# xbee_breakout.net
KiCad netlist of a schematic drawn in EAGLE
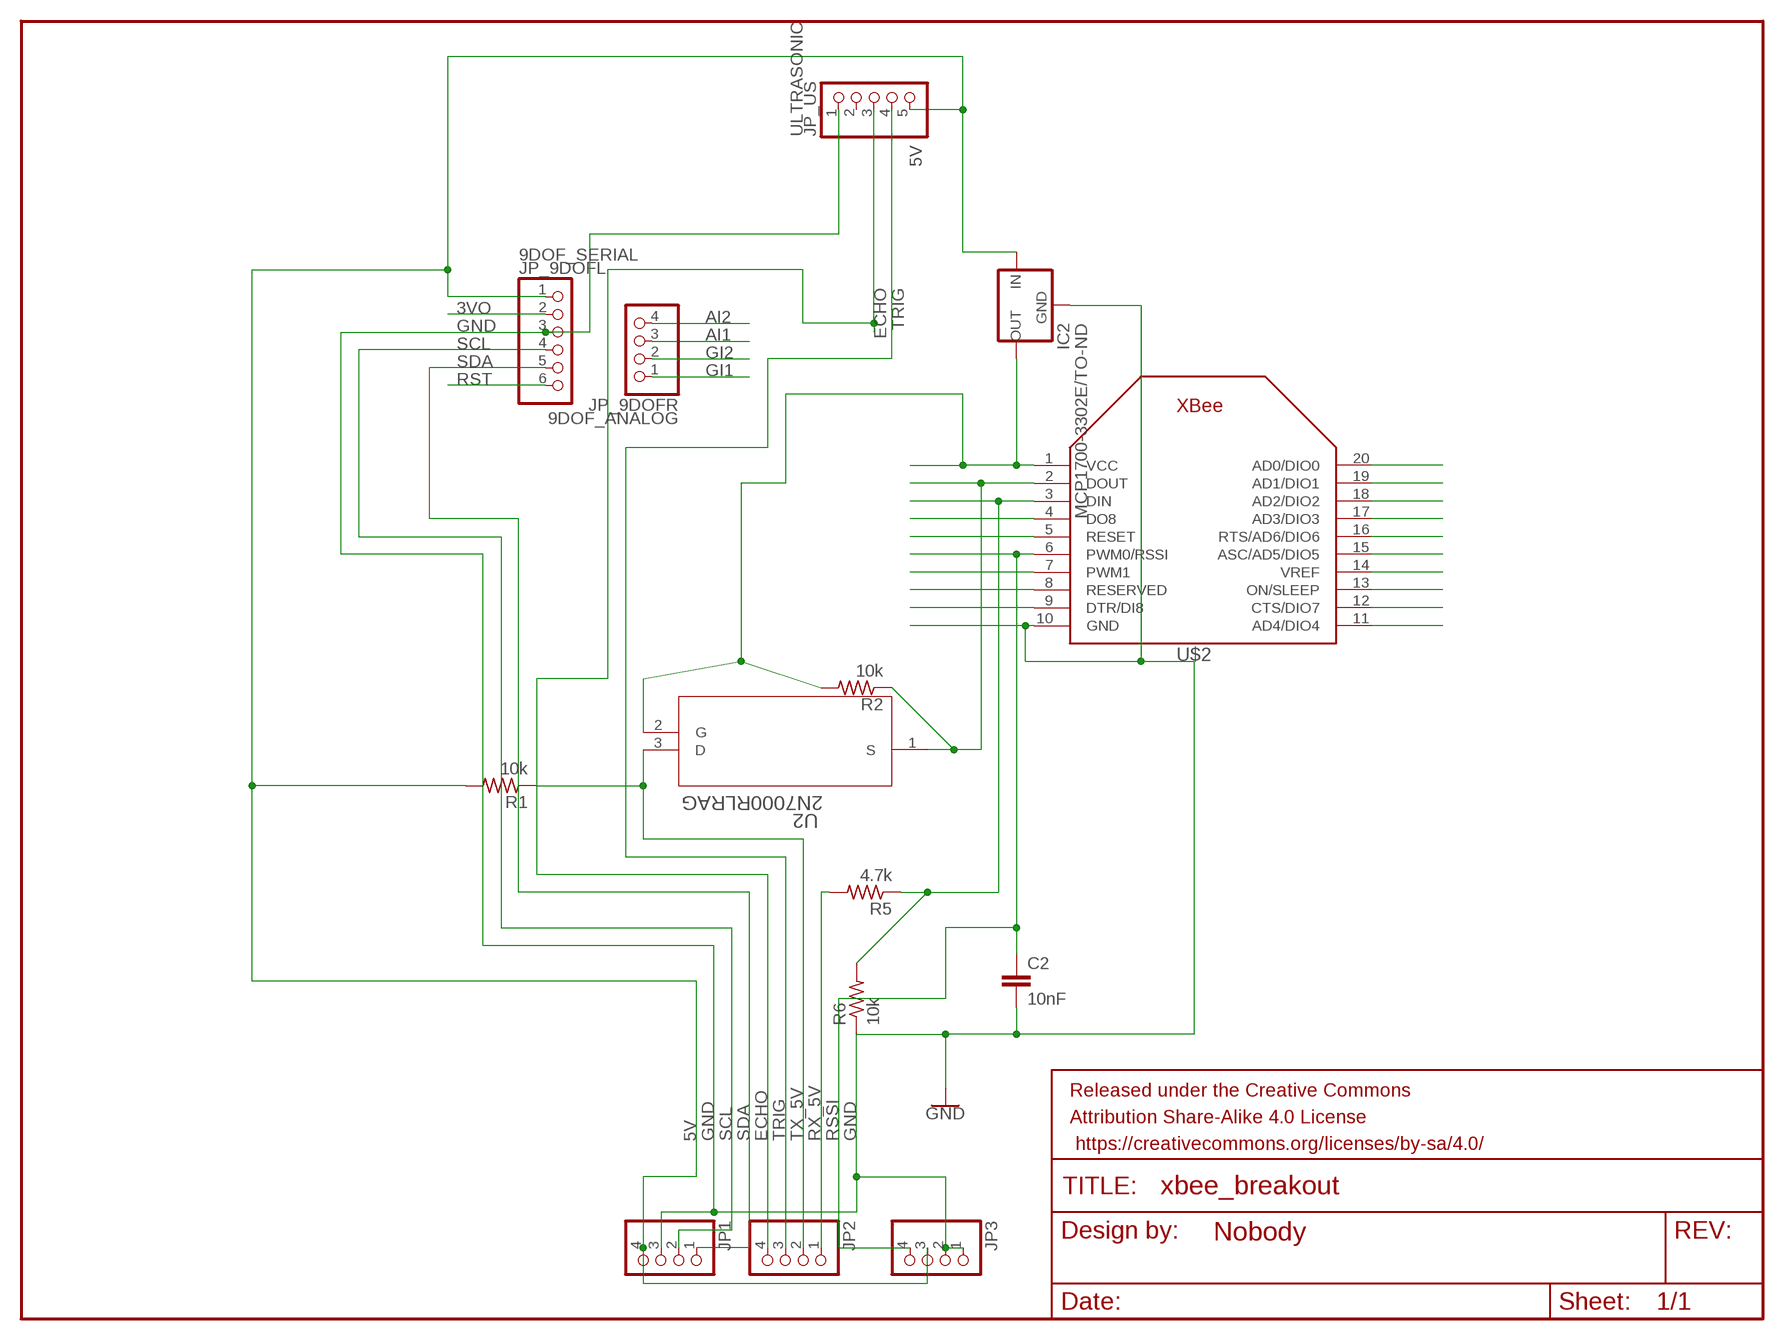
[diagram p0: schematic, sheet 1]

(export (version "E")
  (design (tool "Eeschema 10.0.6"))
  (components
    (comp (ref "C2")
      (value "10nF")
      (footprint "eagle-import:CAP-PTH-10MM")
      (libsource (lib "eagle-import") (part "10NF-PTH-10MM-10000V-1-%"))
    )
    (comp (ref "FRAME1")
      (value "FRAME-LETTERNO_PACKAGE")
      (footprint "eagle-import:DUMMY")
      (fields (field (name "DESIGNER") "Nobody"))
      (libsource (lib "eagle-import") (part "FRAME-LETTERNO_PACKAGE"))
    )
    (comp (ref "IC2")
      (value "MCP1700-3302E/TO-ND")
      (footprint "eagle-import:TO92-INLINE")
      (libsource (lib "eagle-import") (part "MCP1700INLINE"))
    )
    (comp (ref "JP1")
      (value "PINHD-1X4")
      (footprint "eagle-import:1X04")
      (libsource (lib "eagle-import") (part "PINHD-1X4"))
    )
    (comp (ref "JP2")
      (value "PINHD-1X4")
      (footprint "eagle-import:1X04")
      (libsource (lib "eagle-import") (part "PINHD-1X4"))
    )
    (comp (ref "JP3")
      (value "PINHD-1X4")
      (footprint "eagle-import:1X04")
      (libsource (lib "eagle-import") (part "PINHD-1X4"))
    )
    (comp (ref "JP_9DOFL")
      (value "PINHD-1X6")
      (footprint "eagle-import:1X06")
      (libsource (lib "eagle-import") (part "PINHD-1X6"))
    )
    (comp (ref "JP_9DOFR")
      (value "PINHD-1X4")
      (footprint "eagle-import:1X04")
      (libsource (lib "eagle-import") (part "PINHD-1X4"))
    )
    (comp (ref "JP_US")
      (value "PINHD-1X5")
      (footprint "eagle-import:1X05")
      (libsource (lib "eagle-import") (part "PINHD-1X5"))
    )
    (comp (ref "R1")
      (value "10k")
      (footprint "eagle-import:0207_12")
      (libsource (lib "eagle-import") (part "R-US_0207/12"))
    )
    (comp (ref "R2")
      (value "10k")
      (footprint "eagle-import:0207_12")
      (libsource (lib "eagle-import") (part "R-US_0207/12"))
    )
    (comp (ref "R5")
      (value "4.7k")
      (footprint "eagle-import:0207_12")
      (libsource (lib "eagle-import") (part "R-US_0207/12"))
    )
    (comp (ref "R6")
      (value "10k")
      (footprint "eagle-import:0207_12")
      (libsource (lib "eagle-import") (part "R-US_0207/12"))
    )
    (comp (ref "U$2")
      (value "XBEE")
      (footprint "eagle-import:XBEE")
      (libsource (lib "eagle-import") (part "XBEE"))
    )
    (comp (ref "U2")
      (value "2N7000RLRAG")
      (footprint "eagle-import:TO-92")
      (libsource (lib "eagle-import") (part "2N7000RLRAG"))
    )
  )
  (nets
    (net (code "1") (name "/3VO") (class "Default")
      (node (ref "JP_9DOFL") (pin "2") (pinfunction "2_2") (pintype "passive"))
    )
    (net (code "2") (name "/5V") (class "Default")
      (node (ref "IC2") (pin "2") (pinfunction "IN_2") (pintype "input"))
      (node (ref "JP1") (pin "4") (pinfunction "4_4") (pintype "passive"))
      (node (ref "JP3") (pin "3") (pinfunction "3_3") (pintype "passive"))
      (node (ref "JP_9DOFL") (pin "1") (pinfunction "1_1") (pintype "passive"))
      (node (ref "JP_US") (pin "5") (pinfunction "5_5") (pintype "passive"))
      (node (ref "R1") (pin "2") (pinfunction "2_2") (pintype "passive"))
    )
    (net (code "3") (name "/AI1") (class "Default")
      (node (ref "JP_9DOFR") (pin "3") (pinfunction "3_3") (pintype "passive"))
    )
    (net (code "4") (name "/AI2") (class "Default")
      (node (ref "JP_9DOFR") (pin "4") (pinfunction "4_4") (pintype "passive"))
    )
    (net (code "5") (name "/ECHO") (class "Default")
      (node (ref "JP2") (pin "4") (pinfunction "4_4") (pintype "passive"))
      (node (ref "JP_US") (pin "3") (pinfunction "3_3") (pintype "passive"))
    )
    (net (code "6") (name "/GI1") (class "Default")
      (node (ref "JP_9DOFR") (pin "1") (pinfunction "1_1") (pintype "passive"))
    )
    (net (code "7") (name "/GI2") (class "Default")
      (node (ref "JP_9DOFR") (pin "2") (pinfunction "2_2") (pintype "passive"))
    )
    (net (code "8") (name "/RSSI") (class "Default")
      (node (ref "C2") (pin "1") (pinfunction "1_1") (pintype "passive"))
      (node (ref "JP3") (pin "4") (pinfunction "4_4") (pintype "passive"))
      (node (ref "U$2") (pin "6") (pinfunction "PWM0/RSSI_6") (pintype "output"))
    )
    (net (code "9") (name "/RST") (class "Default")
      (node (ref "JP_9DOFL") (pin "6") (pinfunction "6_6") (pintype "passive"))
    )
    (net (code "10") (name "/RX_5V") (class "Default")
      (node (ref "JP2") (pin "1") (pinfunction "1_1") (pintype "passive"))
      (node (ref "R5") (pin "2") (pinfunction "2_2") (pintype "passive"))
    )
    (net (code "11") (name "/SCL") (class "Default")
      (node (ref "JP1") (pin "2") (pinfunction "2_2") (pintype "passive"))
      (node (ref "JP_9DOFL") (pin "4") (pinfunction "4_4") (pintype "passive"))
    )
    (net (code "12") (name "/SDA") (class "Default")
      (node (ref "JP1") (pin "1") (pinfunction "1_1") (pintype "passive"))
      (node (ref "JP_9DOFL") (pin "5") (pinfunction "5_5") (pintype "passive"))
    )
    (net (code "13") (name "/TRIG") (class "Default")
      (node (ref "JP2") (pin "3") (pinfunction "3_3") (pintype "passive"))
      (node (ref "JP_US") (pin "4") (pinfunction "4_4") (pintype "passive"))
    )
    (net (code "14") (name "/TX_5V") (class "Default")
      (node (ref "JP2") (pin "2") (pinfunction "2_2") (pintype "passive"))
      (node (ref "R1") (pin "1") (pinfunction "1_1") (pintype "passive"))
      (node (ref "U2") (pin "3") (pinfunction "D_3") (pintype "passive"))
    )
    (net (code "15") (name "GND") (class "Default")
      (node (ref "C2") (pin "2") (pinfunction "2_2") (pintype "passive"))
      (node (ref "IC2") (pin "1") (pinfunction "GND_1") (pintype "input"))
      (node (ref "JP1") (pin "3") (pinfunction "3_3") (pintype "passive"))
      (node (ref "JP3") (pin "1") (pinfunction "1_1") (pintype "passive"))
      (node (ref "JP3") (pin "2") (pinfunction "2_2") (pintype "passive"))
      (node (ref "JP_9DOFL") (pin "3") (pinfunction "3_3") (pintype "passive"))
      (node (ref "JP_US") (pin "1") (pinfunction "1_1") (pintype "passive"))
      (node (ref "R6") (pin "1") (pinfunction "1_1") (pintype "passive"))
      (node (ref "U$2") (pin "10") (pinfunction "GND_10") (pintype "power_in"))
    )
    (net (code "16") (name "Net-(IC2-OUT)") (class "Default")
      (node (ref "IC2") (pin "3") (pinfunction "OUT_3") (pintype "passive"))
      (node (ref "R2") (pin "2") (pinfunction "2_2") (pintype "passive"))
      (node (ref "U$2") (pin "1") (pinfunction "VCC_1") (pintype "power_in"))
      (node (ref "U2") (pin "2") (pinfunction "G_2") (pintype "passive"))
    )
    (net (code "17") (name "Net-(U$2-DIN)") (class "Default")
      (node (ref "R5") (pin "1") (pinfunction "1_1") (pintype "passive"))
      (node (ref "R6") (pin "2") (pinfunction "2_2") (pintype "passive"))
      (node (ref "U$2") (pin "3") (pinfunction "DIN_3") (pintype "input"))
    )
    (net (code "18") (name "Net-(U$2-DOUT)") (class "Default")
      (node (ref "R2") (pin "1") (pinfunction "1_1") (pintype "passive"))
      (node (ref "U$2") (pin "2") (pinfunction "DOUT_2") (pintype "output"))
      (node (ref "U2") (pin "1") (pinfunction "S_1") (pintype "passive"))
    )
    (net (code "19") (name "unconnected-(JP_US-Pad2)") (class "Default")
      (node (ref "JP_US") (pin "2") (pinfunction "2_2") (pintype "passive"))
    )
    (net (code "20") (name "unconnected-(U$2-AD0{slash}DIO0-Pad20)") (class "Default")
      (node (ref "U$2") (pin "20") (pinfunction "AD0/DIO0_20") (pintype "bidirectional"))
    )
    (net (code "21") (name "unconnected-(U$2-AD1{slash}DIO1-Pad19)") (class "Default")
      (node (ref "U$2") (pin "19") (pinfunction "AD1/DIO1_19") (pintype "bidirectional"))
    )
    (net (code "22") (name "unconnected-(U$2-AD2{slash}DIO2-Pad18)") (class "Default")
      (node (ref "U$2") (pin "18") (pinfunction "AD2/DIO2_18") (pintype "bidirectional"))
    )
    (net (code "23") (name "unconnected-(U$2-AD3{slash}DIO3-Pad17)") (class "Default")
      (node (ref "U$2") (pin "17") (pinfunction "AD3/DIO3_17") (pintype "bidirectional"))
    )
    (net (code "24") (name "unconnected-(U$2-AD4{slash}DIO4-Pad11)") (class "Default")
      (node (ref "U$2") (pin "11") (pinfunction "AD4/DIO4_11") (pintype "bidirectional"))
    )
    (net (code "25") (name "unconnected-(U$2-ASC{slash}AD5{slash}DIO5-Pad15)") (class "Default")
      (node (ref "U$2") (pin "15") (pinfunction "ASC/AD5/DIO5_15") (pintype "bidirectional"))
    )
    (net (code "26") (name "unconnected-(U$2-CTS{slash}DIO7-Pad12)") (class "Default")
      (node (ref "U$2") (pin "12") (pinfunction "CTS/DIO7_12") (pintype "bidirectional"))
    )
    (net (code "27") (name "unconnected-(U$2-DO8-Pad4)") (class "Default")
      (node (ref "U$2") (pin "4") (pinfunction "DO8_4") (pintype "output"))
    )
    (net (code "28") (name "unconnected-(U$2-DTR{slash}DI8-Pad9)") (class "Default")
      (node (ref "U$2") (pin "9") (pinfunction "DTR/DI8_9") (pintype "input"))
    )
    (net (code "29") (name "unconnected-(U$2-ON{slash}SLEEP-Pad13)") (class "Default")
      (node (ref "U$2") (pin "13") (pinfunction "ON/SLEEP_13") (pintype "output"))
    )
    (net (code "30") (name "unconnected-(U$2-PWM1-Pad7)") (class "Default")
      (node (ref "U$2") (pin "7") (pinfunction "PWM1_7") (pintype "output"))
    )
    (net (code "31") (name "unconnected-(U$2-RESERVED-Pad8)") (class "Default")
      (node (ref "U$2") (pin "8") (pinfunction "RESERVED_8") (pintype "no_connect"))
    )
    (net (code "32") (name "unconnected-(U$2-RESET-Pad5)") (class "Default")
      (node (ref "U$2") (pin "5") (pinfunction "RESET_5") (pintype "input"))
    )
    (net (code "33") (name "unconnected-(U$2-RTS{slash}AD6{slash}DIO6-Pad16)") (class "Default")
      (node (ref "U$2") (pin "16") (pinfunction "RTS/AD6/DIO6_16") (pintype "bidirectional"))
    )
    (net (code "34") (name "unconnected-(U$2-VREF-Pad14)") (class "Default")
      (node (ref "U$2") (pin "14") (pinfunction "VREF_14") (pintype "input"))
    )
  )
)
